# SFPextensionSplit.net
KiCad netlist of a schematic drawn in Altium Designer
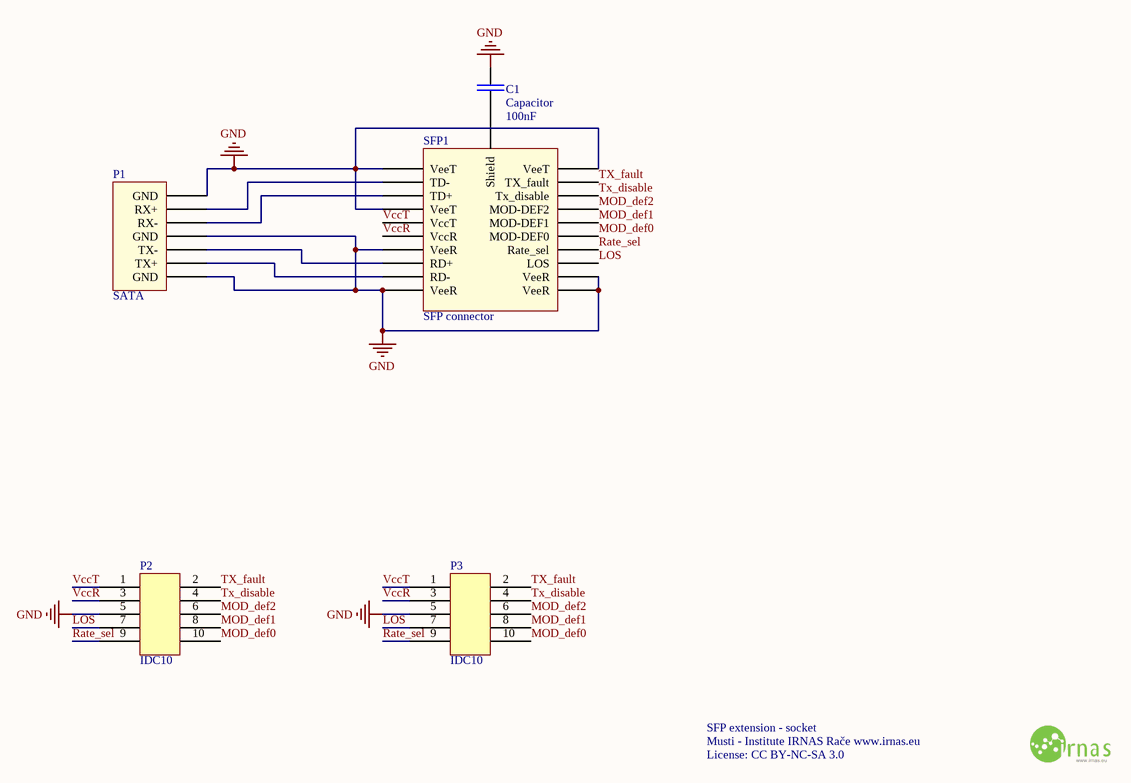
[diagram p0: SFPextensionSplit.SchDoc]

(export (version "E")
  (design (tool "Eeschema 10.0.6"))
  (components
    (comp (ref "C1")
      (value "Capacitor")
      (footprint "RESC2012X06N")
      (description "General capacitor")
      (fields (field (name "ALTIUM_VALUE") "100nF"))
      (libsource (lib "GeneralComponents") (part "Capacitor"))
    )
    (comp (ref "P1")
      (value "SATA")
      (footprint "SATA pcb")
      (description "sata")
      (libsource (lib "GeneralComponents") (part "SATA"))
    )
    (comp (ref "P2")
      (value "IDC10")
      (footprint "IDC10")
      (description "IDC 10pin")
      (libsource (lib "GeneralComponents") (part "IDC10"))
    )
    (comp (ref "P3")
      (value "IDC10")
      (footprint "IDC10")
      (description "IDC 10pin")
      (libsource (lib "GeneralComponents") (part "IDC10"))
    )
    (comp (ref "SFP1")
      (value "SFP connector")
      (footprint "SFP receptacle")
      (libsource (lib "GeneralComponents") (part "SFP connector"))
    )
  )
  (nets
    (net (code "1") (name "/LOS") (class "Default")
      (node (ref "P2") (pin "7") (pinfunction "7_7") (pintype "passive"))
      (node (ref "P3") (pin "7") (pinfunction "7_7") (pintype "passive"))
      (node (ref "SFP1") (pin "8") (pinfunction "LOS_8") (pintype "power_in"))
    )
    (net (code "2") (name "/MOD_def0") (class "Default")
      (node (ref "P2") (pin "10") (pinfunction "10_10") (pintype "passive"))
      (node (ref "P3") (pin "10") (pinfunction "10_10") (pintype "passive"))
      (node (ref "SFP1") (pin "6") (pinfunction "MOD-DEF0_6") (pintype "power_in"))
    )
    (net (code "3") (name "/MOD_def1") (class "Default")
      (node (ref "P2") (pin "8") (pinfunction "8_8") (pintype "passive"))
      (node (ref "P3") (pin "8") (pinfunction "8_8") (pintype "passive"))
      (node (ref "SFP1") (pin "5") (pinfunction "MOD-DEF1_5") (pintype "power_in"))
    )
    (net (code "4") (name "/MOD_def2") (class "Default")
      (node (ref "P2") (pin "6") (pinfunction "6_6") (pintype "passive"))
      (node (ref "P3") (pin "6") (pinfunction "6_6") (pintype "passive"))
      (node (ref "SFP1") (pin "4") (pinfunction "MOD-DEF2_4") (pintype "power_in"))
    )
    (net (code "5") (name "/Rate_sel") (class "Default")
      (node (ref "P2") (pin "9") (pinfunction "9_9") (pintype "passive"))
      (node (ref "P3") (pin "9") (pinfunction "9_9") (pintype "passive"))
      (node (ref "SFP1") (pin "7") (pinfunction "Rate_sel_7") (pintype "power_in"))
    )
    (net (code "6") (name "/TX_fault") (class "Default")
      (node (ref "P2") (pin "2") (pinfunction "2_2") (pintype "passive"))
      (node (ref "P3") (pin "2") (pinfunction "2_2") (pintype "passive"))
      (node (ref "SFP1") (pin "2") (pinfunction "TX_fault_2") (pintype "power_in"))
    )
    (net (code "7") (name "/Tx_disable") (class "Default")
      (node (ref "P2") (pin "4") (pinfunction "4_4") (pintype "passive"))
      (node (ref "P3") (pin "4") (pinfunction "4_4") (pintype "passive"))
      (node (ref "SFP1") (pin "3") (pinfunction "Tx_disable_3") (pintype "power_in"))
    )
    (net (code "8") (name "/VccR") (class "Default")
      (node (ref "P2") (pin "3") (pinfunction "3_3") (pintype "passive"))
      (node (ref "P3") (pin "3") (pinfunction "3_3") (pintype "passive"))
      (node (ref "SFP1") (pin "15") (pinfunction "VccR_15") (pintype "power_in"))
    )
    (net (code "9") (name "/VccT") (class "Default")
      (node (ref "P2") (pin "1") (pinfunction "A_1") (pintype "passive"))
      (node (ref "P3") (pin "1") (pinfunction "A_1") (pintype "passive"))
      (node (ref "SFP1") (pin "16") (pinfunction "VccT_16") (pintype "power_in"))
    )
    (net (code "10") (name "GND") (class "Default")
      (node (ref "C1") (pin "1") (pinfunction "1_1") (pintype "passive"))
      (node (ref "P1") (pin "1") (pinfunction "GND_1") (pintype "power_in"))
      (node (ref "P1") (pin "4") (pinfunction "GND_4") (pintype "power_in"))
      (node (ref "P1") (pin "7") (pinfunction "GND_7") (pintype "power_in"))
      (node (ref "P2") (pin "5") (pinfunction "5_5") (pintype "passive"))
      (node (ref "P3") (pin "5") (pinfunction "5_5") (pintype "passive"))
      (node (ref "SFP1") (pin "1") (pinfunction "VeeT_1") (pintype "power_in"))
      (node (ref "SFP1") (pin "10") (pinfunction "VeeR_10") (pintype "power_in"))
      (node (ref "SFP1") (pin "11") (pinfunction "VeeR_11") (pintype "power_in"))
      (node (ref "SFP1") (pin "14") (pinfunction "VeeR_14") (pintype "power_in"))
      (node (ref "SFP1") (pin "17") (pinfunction "VeeT_17") (pintype "power_in"))
      (node (ref "SFP1") (pin "20") (pinfunction "VeeT_20") (pintype "power_in"))
      (node (ref "SFP1") (pin "9") (pinfunction "VeeR_9") (pintype "power_in"))
    )
    (net (code "11") (name "Net-(P1-RX+)") (class "Default")
      (node (ref "P1") (pin "6") (pinfunction "RX+_6") (pintype "power_in"))
      (node (ref "SFP1") (pin "19") (pinfunction "TD-_19") (pintype "power_in"))
    )
    (net (code "12") (name "Net-(P1-RX-)") (class "Default")
      (node (ref "P1") (pin "5") (pinfunction "RX-_5") (pintype "power_in"))
      (node (ref "SFP1") (pin "18") (pinfunction "TD+_18") (pintype "power_in"))
    )
    (net (code "13") (name "Net-(P1-TX+)") (class "Default")
      (node (ref "P1") (pin "2") (pinfunction "TX+_2") (pintype "power_in"))
      (node (ref "SFP1") (pin "12") (pinfunction "RD-_12") (pintype "power_in"))
    )
    (net (code "14") (name "Net-(P1-TX-)") (class "Default")
      (node (ref "P1") (pin "3") (pinfunction "TX-_3") (pintype "power_in"))
      (node (ref "SFP1") (pin "13") (pinfunction "RD+_13") (pintype "power_in"))
    )
    (net (code "15") (name "Net-(SFP1-Shield)") (class "Default")
      (node (ref "C1") (pin "2") (pinfunction "2_2") (pintype "passive"))
      (node (ref "SFP1") (pin "21") (pinfunction "Shield_21") (pintype "power_in"))
    )
  )
)
